# 7_WiFi.net
KiCad netlist of a schematic drawn in Altium Designer
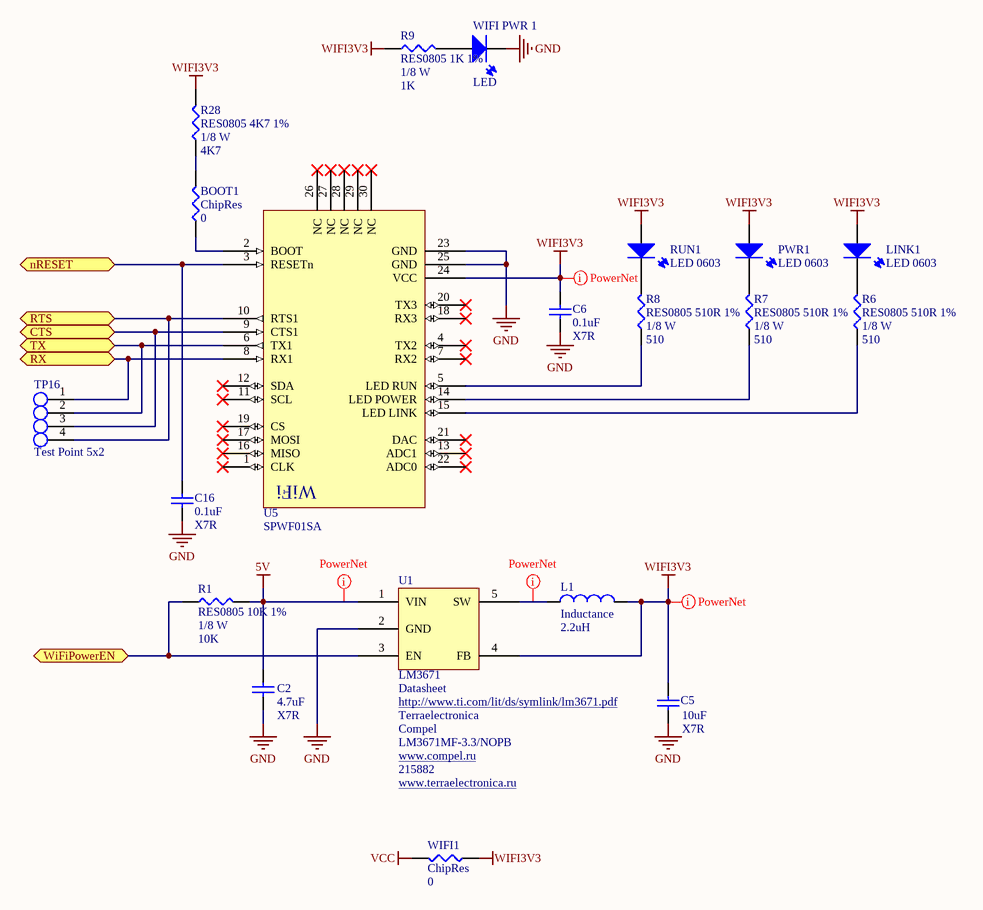
[diagram p0: [7] WiFi.SchDoc]

(export (version "E")
  (design (tool "Eeschema 10.0.6"))
  (components
    (comp (ref "BOOT1")
      (value "ChipRes")
      (footprint "RES0805")
      (description "Chip resistor")
      (fields (field (name "ALTIUM_VALUE") "0"))
      (libsource (lib "Common Devices") (part "ChipRes"))
    )
    (comp (ref "C2")
      (value "4.7uF")
      (footprint "CAP1210")
      (description "Surface-mount ceramic multilayer capacitor")
      (fields (field (name "VOLTAGE") "25V") (field (name "TOLERANCE") "10%") (field (name "TYPE") "X7R"))
      (libsource (lib "Capacitors") (part "ChipCap 4.7uF X7R"))
    )
    (comp (ref "C5")
      (value "10uF")
      (footprint "CAP1210")
      (description "Surface-mount ceramic multilayer capacitor")
      (fields (field (name "VOLTAGE") "25V") (field (name "TOLERANCE") "10%") (field (name "TYPE") "X7R"))
      (libsource (lib "Capacitors") (part "ChipCap 10uF X7R"))
    )
    (comp (ref "C6")
      (value "0.1uF")
      (footprint "CAP0805")
      (description "Surface-mount ceramic multilayer capacitor")
      (fields (field (name "VOLTAGE") "50V") (field (name "TOLERANCE") "5%") (field (name "TYPE") "X7R"))
      (libsource (lib "Capacitors") (part "CAP0805 0.1uF X7R"))
    )
    (comp (ref "C16")
      (value "0.1uF")
      (footprint "CAP0805")
      (description "Surface-mount ceramic multilayer capacitor")
      (fields (field (name "VOLTAGE") "50V") (field (name "TOLERANCE") "5%") (field (name "TYPE") "X7R"))
      (libsource (lib "Capacitors") (part "CAP0805 0.1uF X7R"))
    )
    (comp (ref "L1")
      (value "Inductance")
      (footprint "CDRH2D14")
      (fields (field (name "ALTIUM_VALUE") "2.2uH"))
      (libsource (lib "Common Devices") (part "ChipInductance"))
    )
    (comp (ref "LINK1") (value "LED 0603") (footprint "LED 0603") (libsource (lib "LEDs") (part "LED0603")))
    (comp (ref "PWR1") (value "LED 0603") (footprint "LED 0603") (libsource (lib "LEDs") (part "LED0603")))
    (comp (ref "R1")
      (value "RES0805 10K 1%")
      (footprint "RES0805")
      (description "Think Film Chip resistor")
      (fields
        (field (name "TOLERANCE") "1%")
        (field (name "MANUFACTURER PART NUMBER") "RC0805FR-0710KL")
        (field (name "RATING") "1/8 W")
        (field (name "ALTIUM_VALUE") "10K")
      )
      (libsource (lib "Resistors") (part "RES0805 10K 1%"))
    )
    (comp (ref "R6")
      (value "RES0805 510R 1%")
      (footprint "RES0805")
      (description "Think Film Chip resistor")
      (fields
        (field (name "TOLERANCE") "1%")
        (field (name "MANUFACTURER PART NUMBER") "RC0805FR-07510RL")
        (field (name "RATING") "1/8 W")
        (field (name "ALTIUM_VALUE") "510")
      )
      (libsource (lib "Resistors") (part "RES0805 510R 1%"))
    )
    (comp (ref "R7")
      (value "RES0805 510R 1%")
      (footprint "RES0805")
      (description "Think Film Chip resistor")
      (fields
        (field (name "TOLERANCE") "1%")
        (field (name "MANUFACTURER PART NUMBER") "RC0805FR-07510RL")
        (field (name "RATING") "1/8 W")
        (field (name "ALTIUM_VALUE") "510")
      )
      (libsource (lib "Resistors") (part "RES0805 510R 1%"))
    )
    (comp (ref "R8")
      (value "RES0805 510R 1%")
      (footprint "RES0805")
      (description "Think Film Chip resistor")
      (fields
        (field (name "TOLERANCE") "1%")
        (field (name "MANUFACTURER PART NUMBER") "RC0805FR-07510RL")
        (field (name "RATING") "1/8 W")
        (field (name "ALTIUM_VALUE") "510")
      )
      (libsource (lib "Resistors") (part "RES0805 510R 1%"))
    )
    (comp (ref "R9")
      (value "RES0805 1K 1%")
      (footprint "RES0805")
      (description "Think Film Chip resistor")
      (fields
        (field (name "TOLERANCE") "1%")
        (field (name "MANUFACTURER PART NUMBER") "RC0805FR-071KL")
        (field (name "RATING") "1/8 W")
        (field (name "ALTIUM_VALUE") "1K")
      )
      (libsource (lib "Resistors") (part "RES0805 1K 1%"))
    )
    (comp (ref "R28")
      (value "RES0805 4K7 1%")
      (footprint "RES0805")
      (description "Think Film Chip resistor")
      (fields
        (field (name "TOLERANCE") "1%")
        (field (name "MANUFACTURER PART NUMBER") "RC0805FR-074K7L")
        (field (name "RATING") "1/8 W")
        (field (name "ALTIUM_VALUE") "4K7")
      )
      (libsource (lib "Resistors") (part "RES0805 4K7 1%"))
    )
    (comp (ref "RUN1") (value "LED 0603") (footprint "LED 0603") (libsource (lib "LEDs") (part "LED0603")))
    (comp (ref "TP16")
      (value "Test Point 5x2")
      (footprint "PG-1.5-13.5-4P-2.54PH")
      (libsource (lib "Connectors") (part "PG-1.5-13.5-4P-2.54PH"))
    )
    (comp (ref "U1")
      (value "LM3671")
      (footprint "SOT23-5")
      (description "600-mA Step-Down DC-DC Converter")
      (fields
        (field (name "COMPONENTLINK1DESCRIPTION") "Datasheet")
        (field (name "COMPONENTLINK1URL") "http://www.ti.com/lit/ds/symlink/lm3671.pdf")
        (field (name "SUPPLIER 1") "Terraelectronica")
        (field (name "SUPPLIER 2") "Compel")
        (field (name "SUPPLIER PART NUMBER 2") "LM3671MF-3.3/NOPB")
        (field (name "SUPPLIER URL 2") "www.compel.ru")
        (field (name "SUPPLIER PART NUMBER 1") "215882")
        (field (name "SUPPLIER URL 1") "www.terraelectronica.ru")
      )
      (libsource (lib "TI DC-DC Convertors") (part "LM3671MF"))
    )
    (comp (ref "U5")
      (value "SPWF01SA")
      (footprint "SPWF01SA")
      (description "Serial-to-Wi-Fi b/g/n intelligent module")
      (libsource (lib "ST WiFi") (part "SPWF01"))
    )
    (comp (ref "WIFI PWR 1") (value "LED") (footprint "PLCC-2") (libsource (lib "LEDs") (part "LED0603")))
    (comp (ref "WIFI1")
      (value "ChipRes")
      (footprint "RES0805")
      (description "Chip resistor")
      (fields (field (name "ALTIUM_VALUE") "0"))
      (libsource (lib "Common Devices") (part "ChipRes"))
    )
  )
  (nets
    (net (code "1") (name "/CTS") (class "Default")
      (node (ref "TP16") (pin "3") (pinfunction "3_3") (pintype "passive"))
      (node (ref "U5") (pin "9") (pinfunction "CTS1_9") (pintype "input"))
    )
    (net (code "2") (name "/RTS") (class "Default")
      (node (ref "TP16") (pin "4") (pinfunction "4_4") (pintype "passive"))
      (node (ref "U5") (pin "10") (pinfunction "RTS1_10") (pintype "output"))
    )
    (net (code "3") (name "/RX") (class "Default")
      (node (ref "TP16") (pin "1") (pinfunction "1_1") (pintype "passive"))
      (node (ref "U5") (pin "8") (pinfunction "RX1_8") (pintype "input"))
    )
    (net (code "4") (name "/TX") (class "Default")
      (node (ref "TP16") (pin "2") (pinfunction "2_2") (pintype "passive"))
      (node (ref "U5") (pin "6") (pinfunction "TX1_6") (pintype "output"))
    )
    (net (code "5") (name "/WiFiPowerEN") (class "Default")
      (node (ref "R1") (pin "1") (pintype "passive"))
      (node (ref "U1") (pin "3") (pinfunction "EN_3") (pintype "passive"))
    )
    (net (code "6") (name "/nRESET") (class "Default")
      (node (ref "C16") (pin "1") (pinfunction "1_1") (pintype "passive"))
      (node (ref "U5") (pin "3") (pinfunction "RESETn_3") (pintype "input"))
    )
    (net (code "7") (name "5V") (class "Default")
      (node (ref "C2") (pin "2") (pinfunction "2_2") (pintype "passive"))
      (node (ref "R1") (pin "2") (pintype "passive"))
      (node (ref "U1") (pin "1") (pinfunction "VIN_1") (pintype "passive"))
    )
    (net (code "8") (name "GND") (class "Default")
      (node (ref "C16") (pin "2") (pinfunction "2_2") (pintype "passive"))
      (node (ref "C2") (pin "1") (pinfunction "1_1") (pintype "passive"))
      (node (ref "C5") (pin "1") (pinfunction "1_1") (pintype "passive"))
      (node (ref "C6") (pin "2") (pinfunction "2_2") (pintype "passive"))
      (node (ref "U1") (pin "2") (pinfunction "GND_2") (pintype "passive"))
      (node (ref "U5") (pin "23") (pinfunction "GND_23") (pintype "passive"))
      (node (ref "U5") (pin "25") (pinfunction "GND_25") (pintype "passive"))
      (node (ref "WIFI PWR 1") (pin "1") (pinfunction "1_1") (pintype "passive"))
    )
    (net (code "9") (name "Net-(BOOT1-Pad1)") (class "Default")
      (node (ref "BOOT1") (pin "1") (pintype "passive"))
      (node (ref "R28") (pin "1") (pintype "passive"))
    )
    (net (code "10") (name "Net-(LINK1-Pad1)") (class "Default")
      (node (ref "LINK1") (pin "1") (pinfunction "1_1") (pintype "passive"))
      (node (ref "R6") (pin "2") (pintype "passive"))
    )
    (net (code "11") (name "Net-(PWR1-Pad1)") (class "Default")
      (node (ref "PWR1") (pin "1") (pinfunction "1_1") (pintype "passive"))
      (node (ref "R7") (pin "2") (pintype "passive"))
    )
    (net (code "12") (name "Net-(R8-Pad2)") (class "Default")
      (node (ref "R8") (pin "2") (pintype "passive"))
      (node (ref "RUN1") (pin "1") (pinfunction "1_1") (pintype "passive"))
    )
    (net (code "13") (name "Net-(R9-Pad2)") (class "Default")
      (node (ref "R9") (pin "2") (pintype "passive"))
      (node (ref "WIFI PWR 1") (pin "2") (pinfunction "2_2") (pintype "passive"))
    )
    (net (code "14") (name "Net-(U1-SW)") (class "Default")
      (node (ref "L1") (pin "2") (pintype "passive"))
      (node (ref "U1") (pin "5") (pinfunction "SW_5") (pintype "passive"))
    )
    (net (code "15") (name "Net-(U5-BOOT)") (class "Default")
      (node (ref "BOOT1") (pin "2") (pintype "passive"))
      (node (ref "U5") (pin "2") (pinfunction "BOOT_2") (pintype "input"))
    )
    (net (code "16") (name "Net-(U5-LED_LINK)") (class "Default")
      (node (ref "R6") (pin "1") (pintype "passive"))
      (node (ref "U5") (pin "15") (pinfunction "LED_LINK_15") (pintype "bidirectional"))
    )
    (net (code "17") (name "Net-(U5-LED_POWER)") (class "Default")
      (node (ref "R7") (pin "1") (pintype "passive"))
      (node (ref "U5") (pin "14") (pinfunction "LED_POWER_14") (pintype "bidirectional"))
    )
    (net (code "18") (name "Net-(U5-LED_RUN)") (class "Default")
      (node (ref "R8") (pin "1") (pintype "passive"))
      (node (ref "U5") (pin "5") (pinfunction "LED_RUN_5") (pintype "bidirectional"))
    )
    (net (code "19") (name "VCC") (class "Default") (node (ref "WIFI1") (pin "2") (pintype "passive")))
    (net (code "20") (name "WIFI3V3") (class "Default")
      (node (ref "C5") (pin "2") (pinfunction "2_2") (pintype "passive"))
      (node (ref "C6") (pin "1") (pinfunction "1_1") (pintype "passive"))
      (node (ref "L1") (pin "1") (pintype "passive"))
      (node (ref "LINK1") (pin "2") (pinfunction "2_2") (pintype "passive"))
      (node (ref "PWR1") (pin "2") (pinfunction "2_2") (pintype "passive"))
      (node (ref "R28") (pin "2") (pintype "passive"))
      (node (ref "R9") (pin "1") (pintype "passive"))
      (node (ref "RUN1") (pin "2") (pinfunction "2_2") (pintype "passive"))
      (node (ref "U1") (pin "4") (pinfunction "FB_4") (pintype "passive"))
      (node (ref "U5") (pin "24") (pinfunction "VCC_24") (pintype "power_in"))
      (node (ref "WIFI1") (pin "1") (pintype "passive"))
    )
    (net (code "21") (name "unconnected-(U5-ADC0-Pad22)") (class "Default")
      (node (ref "U5") (pin "22") (pinfunction "ADC0_22") (pintype "bidirectional+no_connect"))
    )
    (net (code "22") (name "unconnected-(U5-ADC1-Pad13)") (class "Default")
      (node (ref "U5") (pin "13") (pinfunction "ADC1_13") (pintype "bidirectional+no_connect"))
    )
    (net (code "23") (name "unconnected-(U5-CLK-Pad1)") (class "Default")
      (node (ref "U5") (pin "1") (pinfunction "CLK_1") (pintype "bidirectional+no_connect"))
    )
    (net (code "24") (name "unconnected-(U5-CS-Pad19)") (class "Default")
      (node (ref "U5") (pin "19") (pinfunction "CS_19") (pintype "bidirectional+no_connect"))
    )
    (net (code "25") (name "unconnected-(U5-DAC-Pad21)") (class "Default")
      (node (ref "U5") (pin "21") (pinfunction "DAC_21") (pintype "bidirectional+no_connect"))
    )
    (net (code "26") (name "unconnected-(U5-MISO-Pad16)") (class "Default")
      (node (ref "U5") (pin "16") (pinfunction "MISO_16") (pintype "bidirectional+no_connect"))
    )
    (net (code "27") (name "unconnected-(U5-MOSI-Pad17)") (class "Default")
      (node (ref "U5") (pin "17") (pinfunction "MOSI_17") (pintype "bidirectional+no_connect"))
    )
    (net (code "28") (name "unconnected-(U5-NC-Pad26)") (class "Default")
      (node (ref "U5") (pin "26") (pinfunction "NC_26") (pintype "passive+no_connect"))
    )
    (net (code "29") (name "unconnected-(U5-NC-Pad27)") (class "Default")
      (node (ref "U5") (pin "27") (pinfunction "NC_27") (pintype "passive+no_connect"))
    )
    (net (code "30") (name "unconnected-(U5-NC-Pad28)") (class "Default")
      (node (ref "U5") (pin "28") (pinfunction "NC_28") (pintype "passive+no_connect"))
    )
    (net (code "31") (name "unconnected-(U5-NC-Pad29)") (class "Default")
      (node (ref "U5") (pin "29") (pinfunction "NC_29") (pintype "passive+no_connect"))
    )
    (net (code "32") (name "unconnected-(U5-NC-Pad30)") (class "Default")
      (node (ref "U5") (pin "30") (pinfunction "NC_30") (pintype "passive+no_connect"))
    )
    (net (code "33") (name "unconnected-(U5-RX2-Pad7)") (class "Default")
      (node (ref "U5") (pin "7") (pinfunction "RX2_7") (pintype "bidirectional+no_connect"))
    )
    (net (code "34") (name "unconnected-(U5-RX3-Pad18)") (class "Default")
      (node (ref "U5") (pin "18") (pinfunction "RX3_18") (pintype "bidirectional+no_connect"))
    )
    (net (code "35") (name "unconnected-(U5-SCL-Pad11)") (class "Default")
      (node (ref "U5") (pin "11") (pinfunction "SCL_11") (pintype "bidirectional+no_connect"))
    )
    (net (code "36") (name "unconnected-(U5-SDA-Pad12)") (class "Default")
      (node (ref "U5") (pin "12") (pinfunction "SDA_12") (pintype "bidirectional+no_connect"))
    )
    (net (code "37") (name "unconnected-(U5-TX2-Pad4)") (class "Default")
      (node (ref "U5") (pin "4") (pinfunction "TX2_4") (pintype "bidirectional+no_connect"))
    )
    (net (code "38") (name "unconnected-(U5-TX3-Pad20)") (class "Default")
      (node (ref "U5") (pin "20") (pinfunction "TX3_20") (pintype "bidirectional+no_connect"))
    )
  )
)
